# AzizCanHAMASOGLU.net
KiCad netlist of a schematic drawn in EAGLE
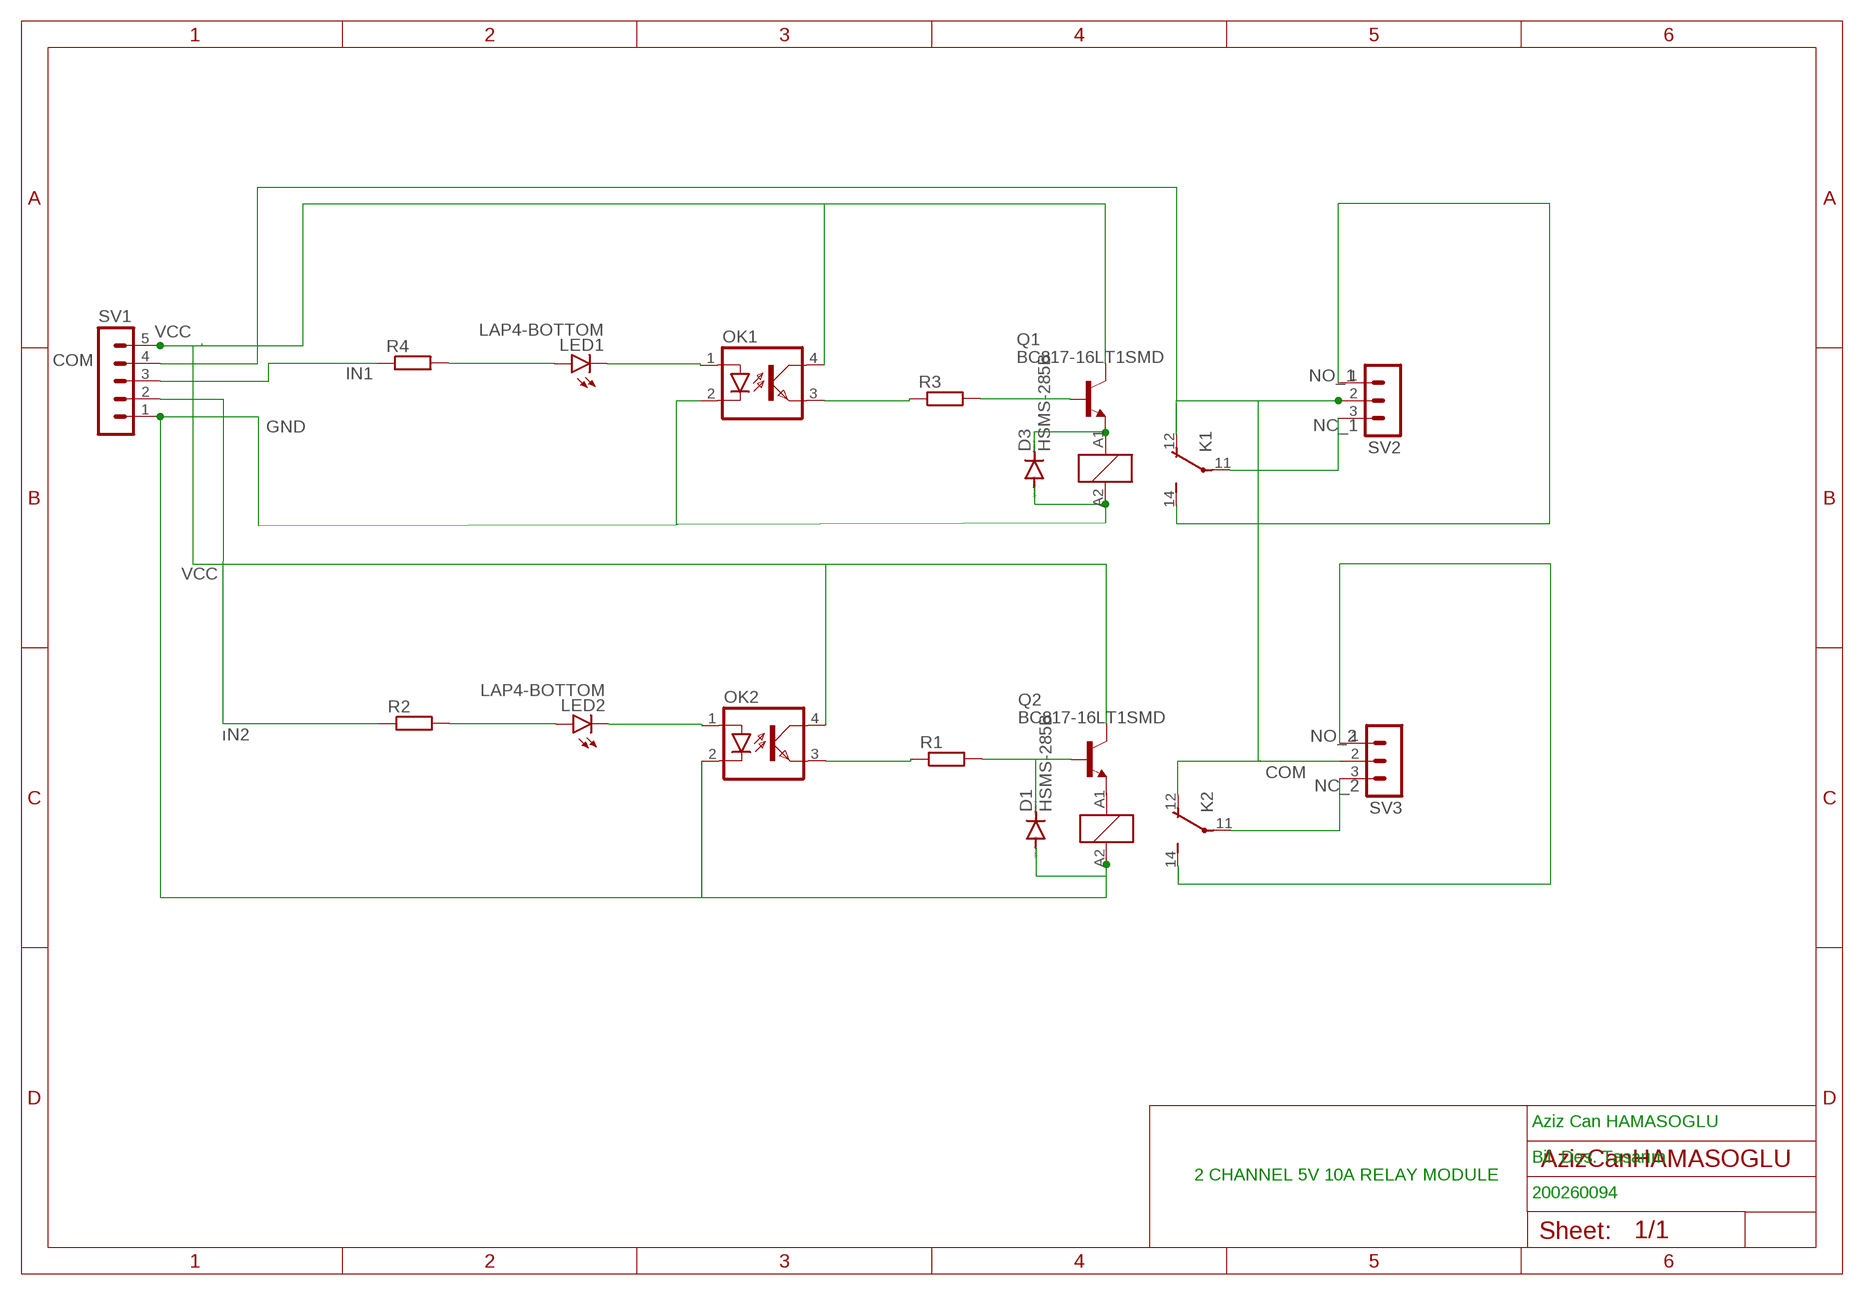
[diagram p0: schematic, sheet 1]

(export (version "E")
  (design (tool "Eeschema 10.0.6"))
  (components
    (comp (ref "D1")
      (value "HSMS-285B")
      (footprint "eagle-import:SOT323")
      (libsource (lib "eagle-import") (part "HSMS-285B"))
    )
    (comp (ref "D3")
      (value "HSMS-285B")
      (footprint "eagle-import:SOT323")
      (libsource (lib "eagle-import") (part "HSMS-285B"))
    )
    (comp (ref "K1")
      (value "RY210005")
      (footprint "eagle-import:RY-II")
      (fields (field (name "MF") "TYCO ELECTRONICS"))
      (libsource (lib "eagle-import") (part "RY?120005"))
    )
    (comp (ref "K2")
      (value "RY210005")
      (footprint "eagle-import:RY-II")
      (fields (field (name "MF") "TYCO ELECTRONICS"))
      (libsource (lib "eagle-import") (part "RY?120005"))
    )
    (comp (ref "LED1")
      (value "LAP4-BOTTOM")
      (footprint "eagle-import:P47F-BOTTOM")
      (libsource (lib "eagle-import") (part "P4-BOTTOMLA"))
    )
    (comp (ref "LED2")
      (value "LAP4-BOTTOM")
      (footprint "eagle-import:P47F-BOTTOM")
      (libsource (lib "eagle-import") (part "P4-BOTTOMLA"))
    )
    (comp (ref "OK1")
      (value "PC817")
      (footprint "eagle-import:DIL04")
      (fields (field (name "MPN") "PC817X4J000F"))
      (libsource (lib "eagle-import") (part "PC817"))
    )
    (comp (ref "OK2")
      (value "PC817")
      (footprint "eagle-import:DIL04")
      (fields (field (name "MPN") "PC817X4J000F"))
      (libsource (lib "eagle-import") (part "PC817"))
    )
    (comp (ref "Q1")
      (value "BC817-16LT1SMD")
      (footprint "eagle-import:SOT23-BEC")
      (libsource (lib "eagle-import") (part "BC817SMD-16LT1"))
    )
    (comp (ref "Q2")
      (value "BC817-16LT1SMD")
      (footprint "eagle-import:SOT23-BEC")
      (libsource (lib "eagle-import") (part "BC817SMD-16LT1"))
    )
    (comp (ref "R1")
      (value "R-EU_M1206")
      (footprint "eagle-import:M1206")
      (libsource (lib "eagle-import") (part "R-EU_M1206"))
    )
    (comp (ref "R2")
      (value "R-EU_M1206")
      (footprint "eagle-import:M1206")
      (libsource (lib "eagle-import") (part "R-EU_M1206"))
    )
    (comp (ref "R3")
      (value "R-EU_M1206")
      (footprint "eagle-import:M1206")
      (libsource (lib "eagle-import") (part "R-EU_M1206"))
    )
    (comp (ref "R4")
      (value "R-EU_M1206")
      (footprint "eagle-import:M1206")
      (libsource (lib "eagle-import") (part "R-EU_M1206"))
    )
    (comp (ref "SV1")
      (value "MA05-1")
      (footprint "eagle-import:MA05-1")
      (libsource (lib "eagle-import") (part "MA05-1"))
    )
    (comp (ref "SV2")
      (value "MA03-1")
      (footprint "eagle-import:MA03-1")
      (libsource (lib "eagle-import") (part "MA03-1"))
    )
    (comp (ref "SV3")
      (value "MA03-1")
      (footprint "eagle-import:MA03-1")
      (libsource (lib "eagle-import") (part "MA03-1"))
    )
  )
  (nets
    (net (code "1") (name "/COM") (class "Default")
      (node (ref "K1") (pin "12") (pinfunction "O_12") (pintype "passive"))
      (node (ref "SV1") (pin "4") (pinfunction "4_4") (pintype "passive"))
      (node (ref "SV2") (pin "2") (pinfunction "2_2") (pintype "passive"))
      (node (ref "SV3") (pin "2") (pinfunction "2_2") (pintype "passive"))
    )
    (net (code "2") (name "/GND") (class "Default")
      (node (ref "D1") (pin "1") (pinfunction "A_1") (pintype "passive"))
      (node (ref "D3") (pin "1") (pinfunction "A_1") (pintype "passive"))
      (node (ref "K1") (pin "A2") (pinfunction "2_A2") (pintype "passive"))
      (node (ref "K2") (pin "A2") (pinfunction "2_A2") (pintype "passive"))
      (node (ref "OK1") (pin "2") (pinfunction "C_2") (pintype "passive"))
      (node (ref "OK2") (pin "2") (pinfunction "C_2") (pintype "passive"))
      (node (ref "SV1") (pin "1") (pinfunction "1_1") (pintype "passive"))
    )
    (net (code "3") (name "/IN1") (class "Default")
      (node (ref "R4") (pin "1") (pinfunction "1_1") (pintype "passive"))
      (node (ref "SV1") (pin "3") (pinfunction "3_3") (pintype "passive"))
    )
    (net (code "4") (name "/NC_1") (class "Default")
      (node (ref "K1") (pin "11") (pinfunction "P_11") (pintype "passive"))
      (node (ref "SV2") (pin "3") (pinfunction "3_3") (pintype "passive"))
    )
    (net (code "5") (name "/NC_2") (class "Default")
      (node (ref "K2") (pin "11") (pinfunction "P_11") (pintype "passive"))
      (node (ref "SV3") (pin "3") (pinfunction "3_3") (pintype "passive"))
    )
    (net (code "6") (name "/NO_1") (class "Default")
      (node (ref "K1") (pin "14") (pinfunction "S_14") (pintype "passive"))
      (node (ref "SV2") (pin "1") (pinfunction "1_1") (pintype "passive"))
    )
    (net (code "7") (name "/NO_2") (class "Default")
      (node (ref "K2") (pin "14") (pinfunction "S_14") (pintype "passive"))
      (node (ref "SV3") (pin "1") (pinfunction "1_1") (pintype "passive"))
    )
    (net (code "8") (name "/VCC") (class "Default")
      (node (ref "OK1") (pin "4") (pinfunction "COL_4") (pintype "passive"))
      (node (ref "OK2") (pin "4") (pinfunction "COL_4") (pintype "passive"))
      (node (ref "Q1") (pin "C") (pinfunction "C_C") (pintype "passive"))
      (node (ref "Q2") (pin "C") (pinfunction "C_C") (pintype "passive"))
      (node (ref "SV1") (pin "5") (pinfunction "5_5") (pintype "passive"))
    )
    (net (code "9") (name "/ıN2") (class "Default")
      (node (ref "R2") (pin "1") (pinfunction "1_1") (pintype "passive"))
      (node (ref "SV1") (pin "2") (pinfunction "2_2") (pintype "passive"))
    )
    (net (code "10") (name "Net-(D1-C)") (class "Default")
      (node (ref "D1") (pin "3") (pinfunction "C_3") (pintype "passive"))
      (node (ref "Q2") (pin "B") (pinfunction "B_B") (pintype "passive"))
      (node (ref "R1") (pin "2") (pinfunction "2_2") (pintype "passive"))
    )
    (net (code "11") (name "Net-(D3-C)") (class "Default")
      (node (ref "D3") (pin "3") (pinfunction "C_3") (pintype "passive"))
      (node (ref "K1") (pin "A1") (pinfunction "1_A1") (pintype "passive"))
      (node (ref "Q1") (pin "E") (pinfunction "E_E") (pintype "passive"))
    )
    (net (code "12") (name "Net-(LED1-PadA)") (class "Default")
      (node (ref "LED1") (pin "A") (pinfunction "A_A") (pintype "passive"))
      (node (ref "R4") (pin "2") (pinfunction "2_2") (pintype "passive"))
    )
    (net (code "13") (name "Net-(LED2-PadA)") (class "Default")
      (node (ref "LED2") (pin "A") (pinfunction "A_A") (pintype "passive"))
      (node (ref "R2") (pin "2") (pinfunction "2_2") (pintype "passive"))
    )
    (net (code "14") (name "Net-(OK1-A)") (class "Default")
      (node (ref "LED1") (pin "C") (pinfunction "C_C") (pintype "passive"))
      (node (ref "OK1") (pin "1") (pinfunction "A_1") (pintype "passive"))
    )
    (net (code "15") (name "Net-(OK1-EMIT)") (class "Default")
      (node (ref "OK1") (pin "3") (pinfunction "EMIT_3") (pintype "passive"))
      (node (ref "R3") (pin "1") (pinfunction "1_1") (pintype "passive"))
    )
    (net (code "16") (name "Net-(OK2-A)") (class "Default")
      (node (ref "LED2") (pin "C") (pinfunction "C_C") (pintype "passive"))
      (node (ref "OK2") (pin "1") (pinfunction "A_1") (pintype "passive"))
    )
    (net (code "17") (name "Net-(OK2-EMIT)") (class "Default")
      (node (ref "OK2") (pin "3") (pinfunction "EMIT_3") (pintype "passive"))
      (node (ref "R1") (pin "1") (pinfunction "1_1") (pintype "passive"))
    )
    (net (code "18") (name "Net-(Q1-PadB)") (class "Default")
      (node (ref "Q1") (pin "B") (pinfunction "B_B") (pintype "passive"))
      (node (ref "R3") (pin "2") (pinfunction "2_2") (pintype "passive"))
    )
    (net (code "19") (name "unconnected-(K2A-1-PadA1)") (class "Default")
      (node (ref "K2") (pin "A1") (pinfunction "1_A1") (pintype "passive"))
    )
    (net (code "20") (name "unconnected-(K2B-O-Pad12)") (class "Default")
      (node (ref "K2") (pin "12") (pinfunction "O_12") (pintype "passive"))
    )
    (net (code "21") (name "unconnected-(Q2-PadE)") (class "Default")
      (node (ref "Q2") (pin "E") (pinfunction "E_E") (pintype "passive"))
    )
  )
)
